# attiniest85-batty-shield-mk-2_2.net
KiCad netlist of a schematic drawn in EAGLE
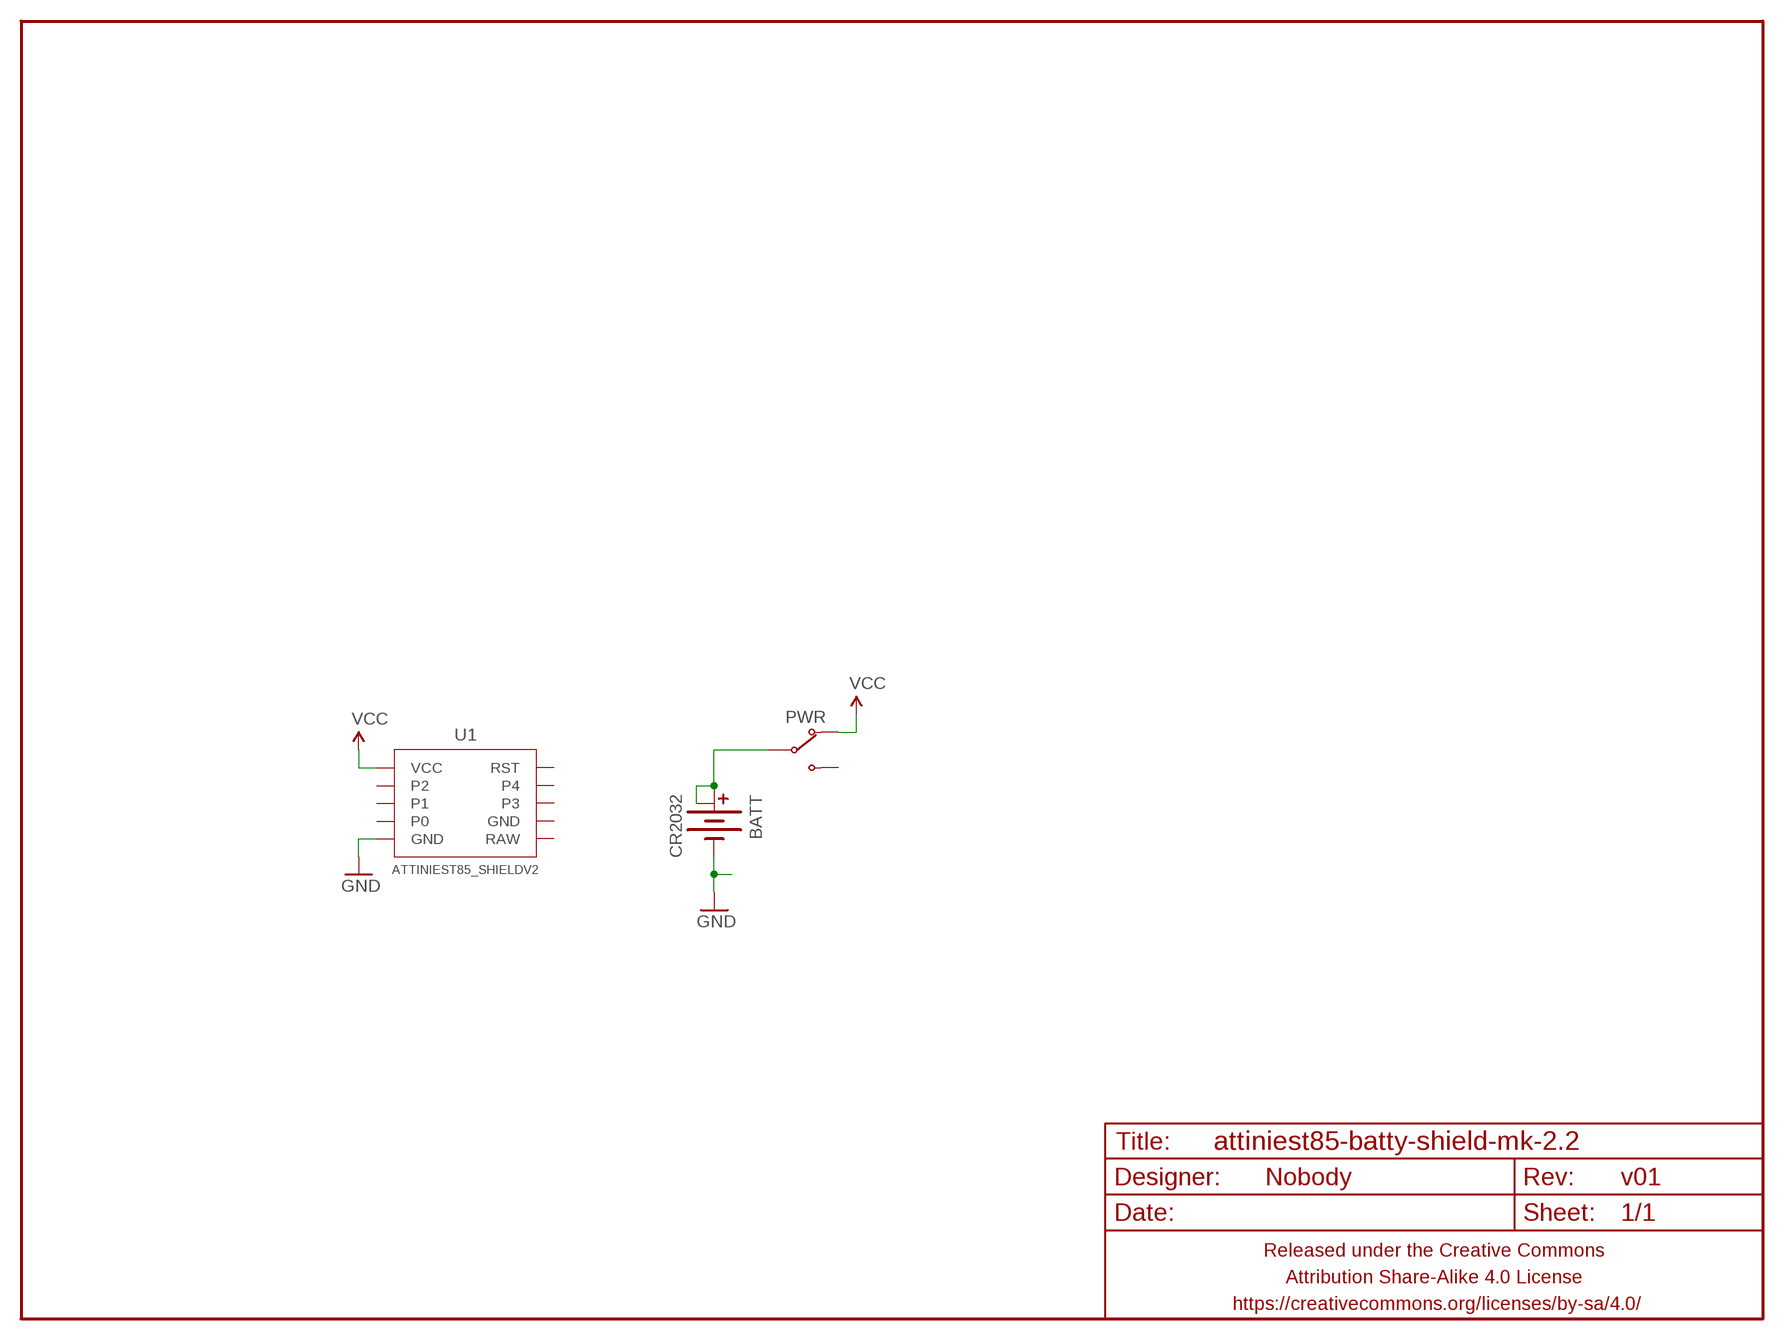
[diagram p0: schematic, sheet 1]

(export (version "E")
  (design (tool "Eeschema 10.0.6"))
  (components
    (comp (ref "BATT")
      (value "CR2032")
      (footprint "eagle-import:BATTCON_20MM_MINE")
      (libsource (lib "eagle-import") (part "BATTERY-COINCR2032_SMD"))
    )
    (comp (ref "FRAME1")
      (value "FRAME-LETTERNO_PACKAGE")
      (footprint "eagle-import:DUMMY")
      (fields (field (name "DESIGNER") "Nobody"))
      (libsource (lib "eagle-import") (part "FRAME-LETTERNO_PACKAGE"))
    )
    (comp (ref "PWR")
      (value "SWITCH-SPDTPTH-RA-2MM")
      (footprint "eagle-import:SPDT-RA-2MM")
      (libsource (lib "eagle-import") (part "SWITCH-SPDTPTH-RA-2MM"))
    )
    (comp (ref "U1")
      (value "ATTINIEST85_SHIELDV2")
      (footprint "eagle-import:ATTINIEST85_SHIELD_V2")
      (libsource (lib "eagle-import") (part "ATTINIEST85_SHIELDV2"))
    )
  )
  (nets
    (net (code "1") (name "GND") (class "Default")
      (node (ref "BATT") (pin "BOTTOM") (pinfunction "-_BOTTOM") (pintype "bidirectional"))
      (node (ref "U1") (pin "GND@2") (pinfunction "GND_GND@2") (pintype "bidirectional"))
    )
    (net (code "2") (name "Net-(BATT-+)") (class "Default")
      (node (ref "BATT") (pin "TOP@1") (pinfunction "+_TOP@1") (pintype "bidirectional"))
      (node (ref "BATT") (pin "TOP@2") (pinfunction "+1_TOP@2") (pintype "bidirectional"))
      (node (ref "PWR") (pin "2") (pinfunction "COM_2") (pintype "passive"))
    )
    (net (code "3") (name "VCC") (class "Default")
      (node (ref "PWR") (pin "1") (pinfunction "NC_1") (pintype "passive"))
      (node (ref "U1") (pin "VCC") (pinfunction "VCC_VCC") (pintype "bidirectional"))
    )
    (net (code "4") (name "unconnected-(PWR-NO-Pad3)") (class "Default")
      (node (ref "PWR") (pin "3") (pinfunction "NO_3") (pintype "passive"))
    )
    (net (code "5") (name "unconnected-(U1-GND-PadGND@1)") (class "Default")
      (node (ref "U1") (pin "GND@1") (pinfunction "GND_GND@1") (pintype "bidirectional"))
    )
    (net (code "6") (name "unconnected-(U1-P0-Pad0)") (class "Default")
      (node (ref "U1") (pin "0") (pinfunction "P0_0") (pintype "bidirectional"))
    )
    (net (code "7") (name "unconnected-(U1-P1-Pad1)") (class "Default")
      (node (ref "U1") (pin "1") (pinfunction "P1_1") (pintype "bidirectional"))
    )
    (net (code "8") (name "unconnected-(U1-P2-Pad2)") (class "Default")
      (node (ref "U1") (pin "2") (pinfunction "P2_2") (pintype "bidirectional"))
    )
    (net (code "9") (name "unconnected-(U1-P3-Pad3)") (class "Default")
      (node (ref "U1") (pin "3") (pinfunction "P3_3") (pintype "bidirectional"))
    )
    (net (code "10") (name "unconnected-(U1-P4-Pad4)") (class "Default")
      (node (ref "U1") (pin "4") (pinfunction "P4_4") (pintype "bidirectional"))
    )
    (net (code "11") (name "unconnected-(U1-PadRAW)") (class "Default")
      (node (ref "U1") (pin "RAW") (pinfunction "RAW_RAW") (pintype "bidirectional"))
    )
    (net (code "12") (name "unconnected-(U1-PadRST)") (class "Default")
      (node (ref "U1") (pin "RST") (pinfunction "RST_RST") (pintype "bidirectional"))
    )
  )
)
